# buttons.net
KiCad netlist of a schematic drawn in EAGLE
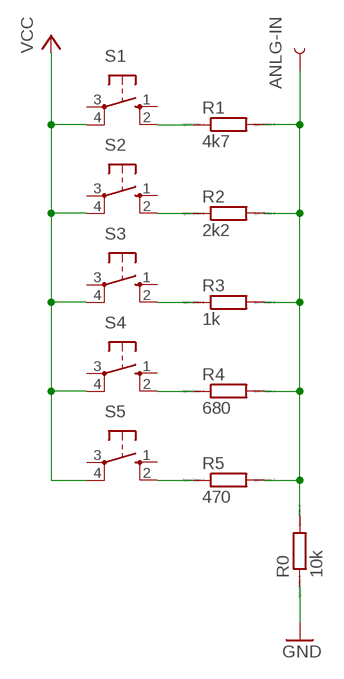
[diagram p0: schematic, sheet 1]

(export (version "E")
  (design (tool "Eeschema 10.0.6"))
  (components
    (comp (ref "ANLG-IN")
      (value "TEST-POINT2")
      (footprint "eagle-import:PAD.02X.02")
      (libsource (lib "eagle-import") (part "TEST-POINT2"))
    )
    (comp (ref "R0")
      (value "10k")
      (footprint "eagle-import:0204_7")
      (libsource (lib "eagle-import") (part "R0204/7"))
    )
    (comp (ref "R1")
      (value "4k7")
      (footprint "eagle-import:0204_7")
      (libsource (lib "eagle-import") (part "R0204/7"))
    )
    (comp (ref "R2")
      (value "2k2")
      (footprint "eagle-import:0204_7")
      (libsource (lib "eagle-import") (part "R0204/7"))
    )
    (comp (ref "R3")
      (value "1k")
      (footprint "eagle-import:0204_7")
      (libsource (lib "eagle-import") (part "R0204/7"))
    )
    (comp (ref "R4")
      (value "680")
      (footprint "eagle-import:0204_7")
      (libsource (lib "eagle-import") (part "R0204/7"))
    )
    (comp (ref "R5")
      (value "470")
      (footprint "eagle-import:0204_7")
      (libsource (lib "eagle-import") (part "R0204/7"))
    )
    (comp (ref "S1")
      (value "10-XX")
      (footprint "eagle-import:B3F-10XX")
      (fields (field (name "MPN") "B3F-1000"))
      (libsource (lib "eagle-import") (part "10-XX"))
    )
    (comp (ref "S2")
      (value "10-XX")
      (footprint "eagle-import:B3F-10XX")
      (fields (field (name "MPN") "B3F-1000"))
      (libsource (lib "eagle-import") (part "10-XX"))
    )
    (comp (ref "S3")
      (value "10-XX")
      (footprint "eagle-import:B3F-10XX")
      (fields (field (name "MPN") "B3F-1000"))
      (libsource (lib "eagle-import") (part "10-XX"))
    )
    (comp (ref "S4")
      (value "10-XX")
      (footprint "eagle-import:B3F-10XX")
      (fields (field (name "MPN") "B3F-1000"))
      (libsource (lib "eagle-import") (part "10-XX"))
    )
    (comp (ref "S5")
      (value "10-XX")
      (footprint "eagle-import:B3F-10XX")
      (fields (field (name "MPN") "B3F-1000"))
      (libsource (lib "eagle-import") (part "10-XX"))
    )
  )
  (nets
    (net (code "1") (name "GND") (class "Default")
      (node (ref "R0") (pin "1") (pinfunction "1_1") (pintype "passive"))
    )
    (net (code "2") (name "Net-(ANLG-IN-1)") (class "Default")
      (node (ref "ANLG-IN") (pin "P$1") (pinfunction "1_P$1") (pintype "bidirectional"))
      (node (ref "R0") (pin "2") (pinfunction "2_2") (pintype "passive"))
      (node (ref "R1") (pin "2") (pinfunction "2_2") (pintype "passive"))
      (node (ref "R2") (pin "2") (pinfunction "2_2") (pintype "passive"))
      (node (ref "R3") (pin "2") (pinfunction "2_2") (pintype "passive"))
      (node (ref "R4") (pin "2") (pinfunction "2_2") (pintype "passive"))
      (node (ref "R5") (pin "2") (pinfunction "2_2") (pintype "passive"))
    )
    (net (code "3") (name "Net-(S1-S1)") (class "Default")
      (node (ref "R1") (pin "1") (pinfunction "1_1") (pintype "passive"))
      (node (ref "S1") (pin "2") (pinfunction "S1_2") (pintype "passive"))
    )
    (net (code "4") (name "Net-(S2-S1)") (class "Default")
      (node (ref "R2") (pin "1") (pinfunction "1_1") (pintype "passive"))
      (node (ref "S2") (pin "2") (pinfunction "S1_2") (pintype "passive"))
    )
    (net (code "5") (name "Net-(S3-S1)") (class "Default")
      (node (ref "R3") (pin "1") (pinfunction "1_1") (pintype "passive"))
      (node (ref "S3") (pin "2") (pinfunction "S1_2") (pintype "passive"))
    )
    (net (code "6") (name "Net-(S4-S1)") (class "Default")
      (node (ref "R4") (pin "1") (pinfunction "1_1") (pintype "passive"))
      (node (ref "S4") (pin "2") (pinfunction "S1_2") (pintype "passive"))
    )
    (net (code "7") (name "Net-(S5-S1)") (class "Default")
      (node (ref "R5") (pin "1") (pinfunction "1_1") (pintype "passive"))
      (node (ref "S5") (pin "2") (pinfunction "S1_2") (pintype "passive"))
    )
    (net (code "8") (name "VCC") (class "Default")
      (node (ref "S1") (pin "4") (pinfunction "P1_4") (pintype "passive"))
      (node (ref "S2") (pin "4") (pinfunction "P1_4") (pintype "passive"))
      (node (ref "S3") (pin "4") (pinfunction "P1_4") (pintype "passive"))
      (node (ref "S4") (pin "4") (pinfunction "P1_4") (pintype "passive"))
      (node (ref "S5") (pin "4") (pinfunction "P1_4") (pintype "passive"))
    )
    (net (code "9") (name "unconnected-(S1-P-Pad3)") (class "Default")
      (node (ref "S1") (pin "3") (pinfunction "P_3") (pintype "passive"))
    )
    (net (code "10") (name "unconnected-(S1-S-Pad1)") (class "Default")
      (node (ref "S1") (pin "1") (pinfunction "S_1") (pintype "passive"))
    )
    (net (code "11") (name "unconnected-(S2-P-Pad3)") (class "Default")
      (node (ref "S2") (pin "3") (pinfunction "P_3") (pintype "passive"))
    )
    (net (code "12") (name "unconnected-(S2-S-Pad1)") (class "Default")
      (node (ref "S2") (pin "1") (pinfunction "S_1") (pintype "passive"))
    )
    (net (code "13") (name "unconnected-(S3-P-Pad3)") (class "Default")
      (node (ref "S3") (pin "3") (pinfunction "P_3") (pintype "passive"))
    )
    (net (code "14") (name "unconnected-(S3-S-Pad1)") (class "Default")
      (node (ref "S3") (pin "1") (pinfunction "S_1") (pintype "passive"))
    )
    (net (code "15") (name "unconnected-(S4-P-Pad3)") (class "Default")
      (node (ref "S4") (pin "3") (pinfunction "P_3") (pintype "passive"))
    )
    (net (code "16") (name "unconnected-(S4-S-Pad1)") (class "Default")
      (node (ref "S4") (pin "1") (pinfunction "S_1") (pintype "passive"))
    )
    (net (code "17") (name "unconnected-(S5-P-Pad3)") (class "Default")
      (node (ref "S5") (pin "3") (pinfunction "P_3") (pintype "passive"))
    )
    (net (code "18") (name "unconnected-(S5-S-Pad1)") (class "Default")
      (node (ref "S5") (pin "1") (pinfunction "S_1") (pintype "passive"))
    )
  )
)
